# Flight_Controller.net
KiCad netlist of a schematic drawn in Altium Designer
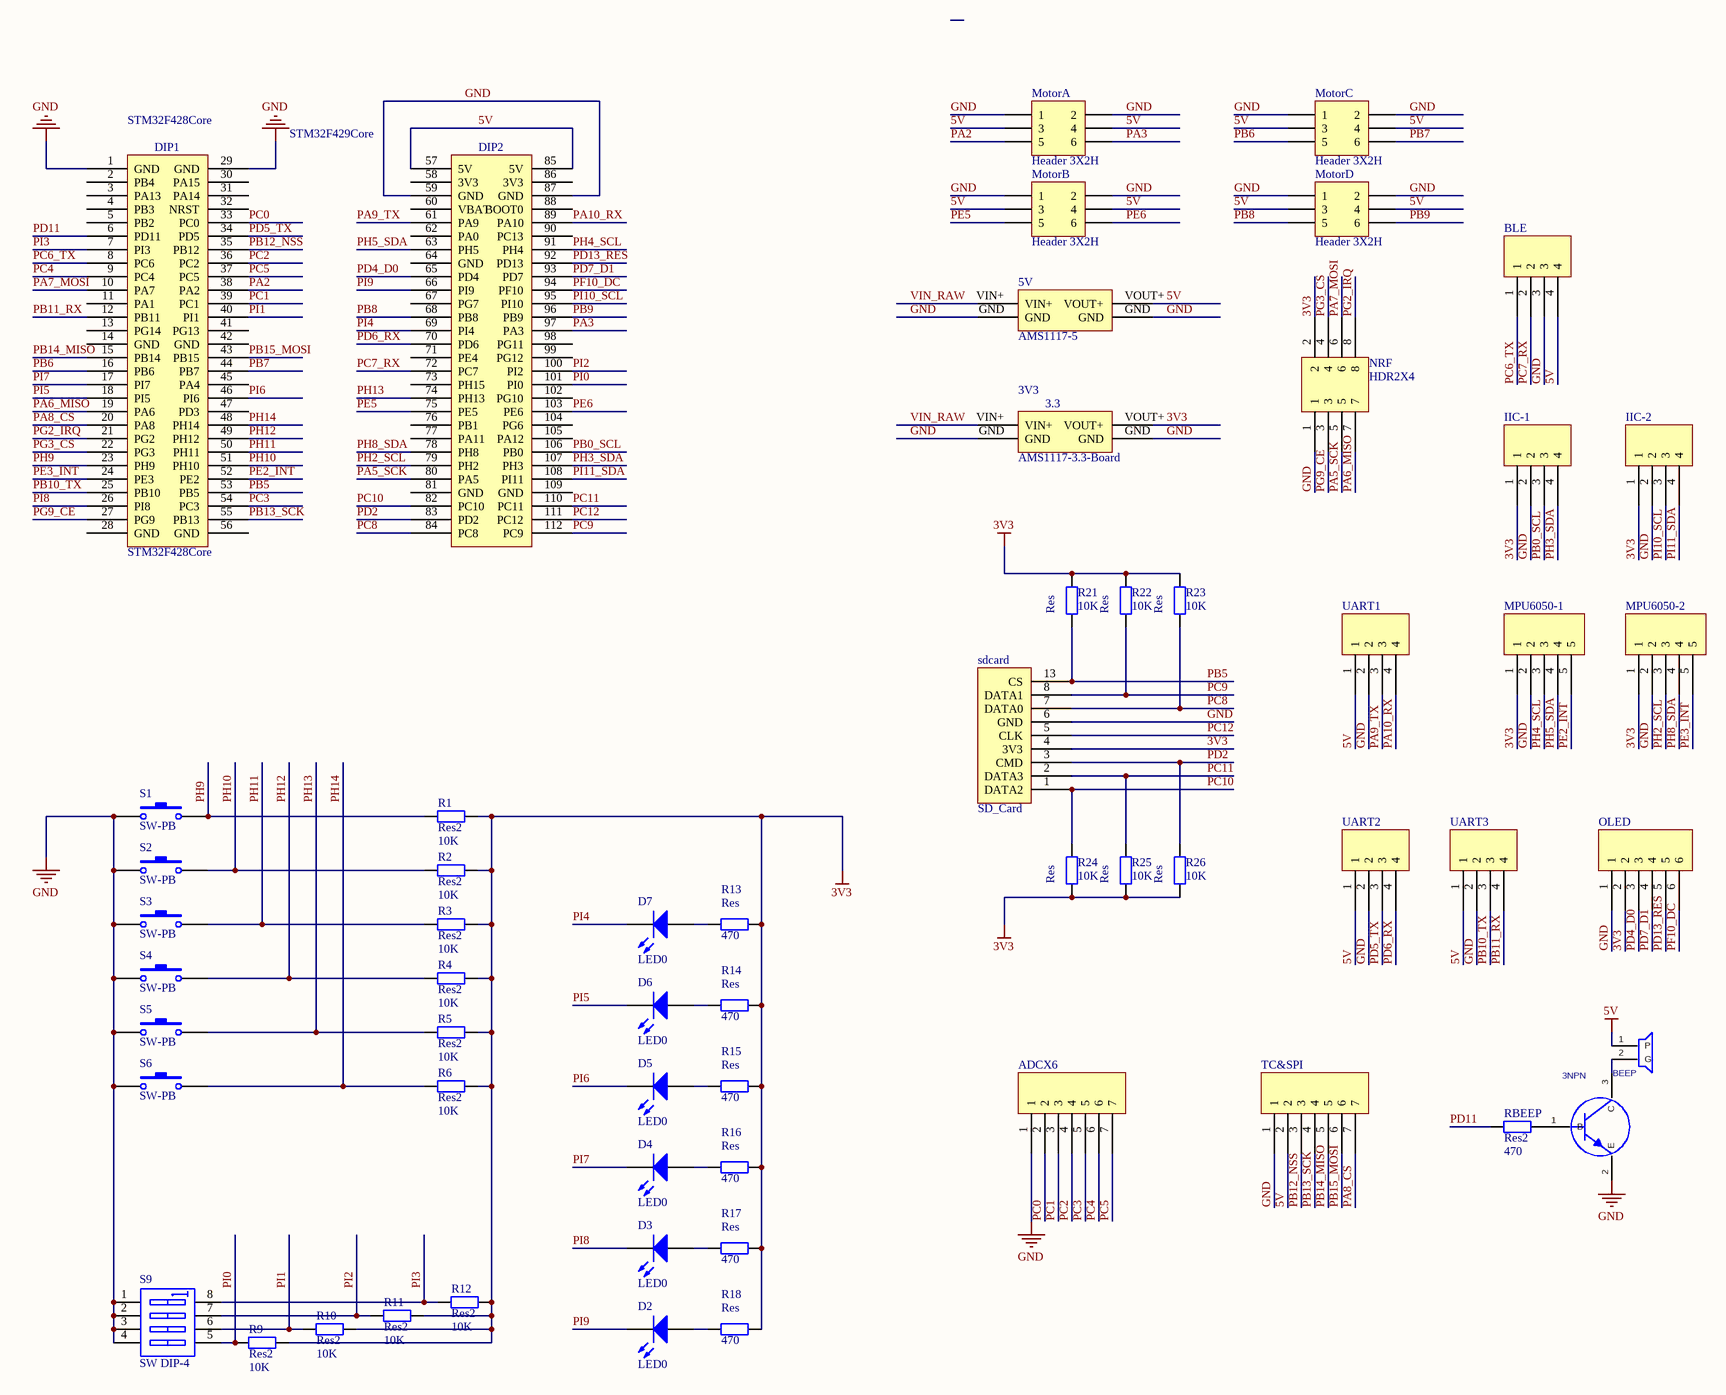
[diagram p0: Flight_Controller.SchDoc]

(export (version "E")
  (design (tool "Eeschema 10.0.6"))
  (components
    (comp (ref "3NPN") (value "NPN") (footprint "3NPN") (libsource (lib "Flight_Controller") (part "3NPN")))
    (comp (ref "3V3")
      (value "AMS1117-3.3-Board")
      (footprint "AMS1117-3.3-Board")
      (libsource (lib "Flight_Controller") (part "AMS1117-3.3-Board"))
    )
    (comp (ref "5V")
      (value "AMS1117-5")
      (footprint "AMS1117-5-Board - duplicate")
      (libsource (lib "Flight_Controller") (part "AMS1117-5"))
    )
    (comp (ref "ADCX6")
      (value "HDR1X7")
      (footprint "HDR1X7")
      (libsource (lib "Flight_Controller") (part "HDR1X7"))
    )
    (comp (ref "BEEP")
      (value "BEEP-9.5X5.5")
      (footprint "BUZZER")
      (libsource (lib "Flight_Controller") (part "BEEP-9.5X5.5"))
    )
    (comp (ref "BLE")
      (value "HDR1X4")
      (footprint "HDR1X4")
      (libsource (lib "Flight_Controller") (part "HDR1X4"))
    )
    (comp (ref "D2")
      (value "LED0")
      (footprint "0805LED")
      (description "Typical INFRARED GaAs LED")
      (fields (field (name "PUBLISHER") "Altium Limited"))
      (libsource (lib "Miscellaneous Devices") (part "LED0"))
    )
    (comp (ref "D3")
      (value "LED0")
      (footprint "0805LED")
      (description "Typical INFRARED GaAs LED")
      (fields (field (name "PUBLISHER") "Altium Limited"))
      (libsource (lib "Miscellaneous Devices") (part "LED0"))
    )
    (comp (ref "D4")
      (value "LED0")
      (footprint "0805LED")
      (description "Typical INFRARED GaAs LED")
      (fields (field (name "PUBLISHER") "Altium Limited"))
      (libsource (lib "Miscellaneous Devices") (part "LED0"))
    )
    (comp (ref "D5")
      (value "LED0")
      (footprint "0805LED")
      (description "Typical INFRARED GaAs LED")
      (fields (field (name "PUBLISHER") "Altium Limited"))
      (libsource (lib "Miscellaneous Devices") (part "LED0"))
    )
    (comp (ref "D6")
      (value "LED0")
      (footprint "0805LED")
      (description "Typical INFRARED GaAs LED")
      (fields (field (name "PUBLISHER") "Altium Limited"))
      (libsource (lib "Miscellaneous Devices") (part "LED0"))
    )
    (comp (ref "D7")
      (value "LED0")
      (footprint "0805LED")
      (description "Typical INFRARED GaAs LED")
      (fields (field (name "PUBLISHER") "Altium Limited"))
      (libsource (lib "Miscellaneous Devices") (part "LED0"))
    )
    (comp (ref "IIC-1")
      (value "HDR1X4")
      (footprint "HDR1X4")
      (libsource (lib "Flight_Controller") (part "HDR1X4"))
    )
    (comp (ref "IIC-2")
      (value "HDR1X4")
      (footprint "HDR1X4")
      (libsource (lib "Flight_Controller") (part "HDR1X4"))
    )
    (comp (ref "MotorA")
      (value "Header 3X2H")
      (footprint "HDR2X3")
      (description "Header, 3-Pin, Dual row, Right Angle")
      (fields (field (name "PUBLISHER") "Altium Limited"))
      (libsource (lib "Miscellaneous Connectors") (part "Header 3X2H"))
    )
    (comp (ref "MotorB")
      (value "Header 3X2H")
      (footprint "HDR2X3")
      (description "Header, 3-Pin, Dual row, Right Angle")
      (fields (field (name "PUBLISHER") "Altium Limited"))
      (libsource (lib "Miscellaneous Connectors") (part "Header 3X2H"))
    )
    (comp (ref "MotorC")
      (value "Header 3X2H")
      (footprint "HDR2X3")
      (description "Header, 3-Pin, Dual row, Right Angle")
      (fields (field (name "PUBLISHER") "Altium Limited"))
      (libsource (lib "Miscellaneous Connectors") (part "Header 3X2H"))
    )
    (comp (ref "MotorD")
      (value "Header 3X2H")
      (footprint "HDR2X3")
      (description "Header, 3-Pin, Dual row, Right Angle")
      (fields (field (name "PUBLISHER") "Altium Limited"))
      (libsource (lib "Miscellaneous Connectors") (part "Header 3X2H"))
    )
    (comp (ref "MPU6050-1")
      (value "HDR1X5")
      (footprint "HDR1X5")
      (libsource (lib "Flight_Controller") (part "HDR1X5"))
    )
    (comp (ref "MPU6050-2")
      (value "HDR1X5")
      (footprint "HDR1X5")
      (libsource (lib "Flight_Controller") (part "HDR1X5"))
    )
    (comp (ref "NRF")
      (value "HDR2X4")
      (footprint "HDR2X4")
      (libsource (lib "Flight_Controller") (part "HDR2X4"))
    )
    (comp (ref "OLED")
      (value "HDR1X6")
      (footprint "HDR1X6")
      (libsource (lib "Flight_Controller") (part "HDR1X6"))
    )
    (comp (ref "R1")
      (value "Res2")
      (footprint "0805")
      (description "Resistor")
      (fields (field (name "ALTIUM_VALUE") "10K") (field (name "PUBLISHER") "Altium Limited"))
      (libsource (lib "Miscellaneous Devices") (part "Res2"))
    )
    (comp (ref "R2")
      (value "Res2")
      (footprint "0805")
      (description "Resistor")
      (fields (field (name "ALTIUM_VALUE") "10K") (field (name "PUBLISHER") "Altium Limited"))
      (libsource (lib "Miscellaneous Devices") (part "Res2"))
    )
    (comp (ref "R3")
      (value "Res2")
      (footprint "0805")
      (description "Resistor")
      (fields (field (name "ALTIUM_VALUE") "10K") (field (name "PUBLISHER") "Altium Limited"))
      (libsource (lib "Miscellaneous Devices") (part "Res2"))
    )
    (comp (ref "R4")
      (value "Res2")
      (footprint "0805")
      (description "Resistor")
      (fields (field (name "ALTIUM_VALUE") "10K") (field (name "PUBLISHER") "Altium Limited"))
      (libsource (lib "Miscellaneous Devices") (part "Res2"))
    )
    (comp (ref "R5")
      (value "Res2")
      (footprint "0805")
      (description "Resistor")
      (fields (field (name "ALTIUM_VALUE") "10K") (field (name "PUBLISHER") "Altium Limited"))
      (libsource (lib "Miscellaneous Devices") (part "Res2"))
    )
    (comp (ref "R6")
      (value "Res2")
      (footprint "0805")
      (description "Resistor")
      (fields (field (name "ALTIUM_VALUE") "10K") (field (name "PUBLISHER") "Altium Limited"))
      (libsource (lib "Miscellaneous Devices") (part "Res2"))
    )
    (comp (ref "R9")
      (value "Res2")
      (footprint "Flight_Controller:0805")
      (description "Resistor")
      (fields (field (name "ALTIUM_VALUE") "10K") (field (name "PUBLISHER") "Altium Limited"))
      (libsource (lib "Miscellaneous Devices") (part "Res2"))
    )
    (comp (ref "R10")
      (value "Res2")
      (footprint "0805")
      (description "Resistor")
      (fields (field (name "ALTIUM_VALUE") "10K") (field (name "PUBLISHER") "Altium Limited"))
      (libsource (lib "Miscellaneous Devices") (part "Res2"))
    )
    (comp (ref "R11")
      (value "Res2")
      (footprint "0805")
      (description "Resistor")
      (fields (field (name "ALTIUM_VALUE") "10K") (field (name "PUBLISHER") "Altium Limited"))
      (libsource (lib "Miscellaneous Devices") (part "Res2"))
    )
    (comp (ref "R12")
      (value "Res2")
      (footprint "0805")
      (description "Resistor")
      (fields (field (name "ALTIUM_VALUE") "10K") (field (name "PUBLISHER") "Altium Limited"))
      (libsource (lib "Miscellaneous Devices") (part "Res2"))
    )
    (comp (ref "R13") (value "470") (footprint "0805") (libsource (lib "") (part "res_1")))
    (comp (ref "R14") (value "470") (footprint "0805") (libsource (lib "") (part "res_1")))
    (comp (ref "R15") (value "470") (footprint "0805") (libsource (lib "") (part "res_1")))
    (comp (ref "R16") (value "470") (footprint "0805") (libsource (lib "") (part "res_1")))
    (comp (ref "R17") (value "470") (footprint "0805") (libsource (lib "") (part "res_1")))
    (comp (ref "R18") (value "470") (footprint "0805") (libsource (lib "") (part "res_1")))
    (comp (ref "R21") (value "10K") (footprint "0805") (libsource (lib "Flight_Controller") (part "res")))
    (comp (ref "R22") (value "10K") (footprint "0805") (libsource (lib "Flight_Controller") (part "res")))
    (comp (ref "R23") (value "10K") (footprint "0805") (libsource (lib "Flight_Controller") (part "res")))
    (comp (ref "R24") (value "10K") (footprint "0805") (libsource (lib "Flight_Controller") (part "res")))
    (comp (ref "R25") (value "10K") (footprint "0805") (libsource (lib "Flight_Controller") (part "res")))
    (comp (ref "R26") (value "10K") (footprint "0805") (libsource (lib "Flight_Controller") (part "res")))
    (comp (ref "RBEEP")
      (value "Res2")
      (footprint "0805")
      (description "Resistor")
      (fields (field (name "ALTIUM_VALUE") "470") (field (name "PUBLISHER") "Altium Limited"))
      (libsource (lib "Miscellaneous Devices") (part "Res2"))
    )
    (comp (ref "S1")
      (value "SW-PB")
      (footprint "Button")
      (description "Switch")
      (fields (field (name "PUBLISHER") "Altium Limited"))
      (libsource (lib "Miscellaneous Devices") (part "SW-PB"))
    )
    (comp (ref "S2")
      (value "SW-PB")
      (footprint "Button")
      (description "Switch")
      (fields (field (name "PUBLISHER") "Altium Limited"))
      (libsource (lib "Miscellaneous Devices") (part "SW-PB"))
    )
    (comp (ref "S3")
      (value "SW-PB")
      (footprint "Button")
      (description "Switch")
      (fields (field (name "PUBLISHER") "Altium Limited"))
      (libsource (lib "Miscellaneous Devices") (part "SW-PB"))
    )
    (comp (ref "S4")
      (value "SW-PB")
      (footprint "Button")
      (description "Switch")
      (fields (field (name "PUBLISHER") "Altium Limited"))
      (libsource (lib "Miscellaneous Devices") (part "SW-PB"))
    )
    (comp (ref "S5")
      (value "SW-PB")
      (footprint "Button")
      (description "Switch")
      (fields (field (name "PUBLISHER") "Altium Limited"))
      (libsource (lib "Miscellaneous Devices") (part "SW-PB"))
    )
    (comp (ref "S6")
      (value "SW-PB")
      (footprint "Button")
      (description "Switch")
      (fields (field (name "PUBLISHER") "Altium Limited"))
      (libsource (lib "Miscellaneous Devices") (part "SW-PB"))
    )
    (comp (ref "S9")
      (value "SW DIP-4")
      (footprint "bmkgtp")
      (description "DIP Switch, 4 Position, SPST")
      (fields (field (name "PUBLISHER") "Altium Limited"))
      (libsource (lib "Miscellaneous Devices") (part "SW DIP-4"))
    )
    (comp (ref "sdcard")
      (value "SD_Card")
      (footprint "SD_Card")
      (libsource (lib "Flight_Controller") (part "SD_Card"))
    )
    (comp (ref "STM32F428Core")
      (value "STM32F428Core")
      (footprint "F429")
      (libsource (lib "Flight_Controller") (part "STM32F428Core"))
    )
    (comp (ref "TC&SPI")
      (value "HDR1X7")
      (footprint "HDR1X7")
      (libsource (lib "Flight_Controller") (part "HDR1X7"))
    )
    (comp (ref "UART1")
      (value "HDR1X4")
      (footprint "HDR1X4")
      (libsource (lib "Flight_Controller") (part "HDR1X4"))
    )
    (comp (ref "UART2")
      (value "HDR1X4")
      (footprint "HDR1X4")
      (libsource (lib "Flight_Controller") (part "HDR1X4"))
    )
    (comp (ref "UART3")
      (value "HDR1X4")
      (footprint "HDR1X4")
      (libsource (lib "Flight_Controller") (part "HDR1X4"))
    )
  )
  (nets
    (net (code "1") (name "/PA2") (class "Default")
      (node (ref "MotorA") (pin "5") (pinfunction "5_5") (pintype "passive"))
      (node (ref "STM32F428Core") (pin "38") (pinfunction "PA2_38") (pintype "passive"))
    )
    (net (code "2") (name "/PA3") (class "Default")
      (node (ref "MotorA") (pin "6") (pinfunction "6_6") (pintype "passive"))
      (node (ref "STM32F428Core") (pin "97") (pinfunction "PA3_97") (pintype "passive"))
    )
    (net (code "3") (name "/PA5_SCK") (class "Default")
      (node (ref "NRF") (pin "5") (pinfunction "5_5") (pintype "passive"))
      (node (ref "STM32F428Core") (pin "80") (pinfunction "PA5_80") (pintype "passive"))
    )
    (net (code "4") (name "/PA6_MISO") (class "Default")
      (node (ref "NRF") (pin "7") (pinfunction "7_7") (pintype "passive"))
      (node (ref "STM32F428Core") (pin "19") (pinfunction "PA6_19") (pintype "passive"))
    )
    (net (code "5") (name "/PA7_MOSI") (class "Default")
      (node (ref "NRF") (pin "6") (pinfunction "6_6") (pintype "passive"))
      (node (ref "STM32F428Core") (pin "10") (pinfunction "PA7_10") (pintype "passive"))
    )
    (net (code "6") (name "/PA8_CS") (class "Default")
      (node (ref "STM32F428Core") (pin "20") (pinfunction "PA8_20") (pintype "passive"))
      (node (ref "TC&SPI") (pin "7") (pinfunction "7_7") (pintype "passive"))
    )
    (net (code "7") (name "/PA9_TX") (class "Default")
      (node (ref "STM32F428Core") (pin "61") (pinfunction "PA9_61") (pintype "passive"))
      (node (ref "UART1") (pin "3") (pinfunction "3_3") (pintype "passive"))
    )
    (net (code "8") (name "/PA10_RX") (class "Default")
      (node (ref "STM32F428Core") (pin "89") (pinfunction "PA10_89") (pintype "passive"))
      (node (ref "UART1") (pin "4") (pinfunction "4_4") (pintype "passive"))
    )
    (net (code "9") (name "/PB0_SCL") (class "Default")
      (node (ref "IIC-1") (pin "3") (pinfunction "3_3") (pintype "passive"))
      (node (ref "STM32F428Core") (pin "106") (pinfunction "PB0_106") (pintype "passive"))
    )
    (net (code "10") (name "/PB5") (class "Default")
      (node (ref "R21") (pin "1") (pinfunction "1_1") (pintype "passive"))
      (node (ref "STM32F428Core") (pin "53") (pinfunction "PB5_53") (pintype "passive"))
      (node (ref "sdcard") (pin "13") (pinfunction "CS_13") (pintype "passive"))
    )
    (net (code "11") (name "/PB6") (class "Default")
      (node (ref "MotorC") (pin "5") (pinfunction "5_5") (pintype "passive"))
      (node (ref "STM32F428Core") (pin "16") (pinfunction "PB6_16") (pintype "passive"))
    )
    (net (code "12") (name "/PB7") (class "Default")
      (node (ref "MotorC") (pin "6") (pinfunction "6_6") (pintype "passive"))
      (node (ref "STM32F428Core") (pin "44") (pinfunction "PB7_44") (pintype "passive"))
    )
    (net (code "13") (name "/PB8") (class "Default")
      (node (ref "MotorD") (pin "5") (pinfunction "5_5") (pintype "passive"))
      (node (ref "STM32F428Core") (pin "68") (pinfunction "PB8_68") (pintype "passive"))
    )
    (net (code "14") (name "/PB9") (class "Default")
      (node (ref "MotorD") (pin "6") (pinfunction "6_6") (pintype "passive"))
      (node (ref "STM32F428Core") (pin "96") (pinfunction "PB9_96") (pintype "passive"))
    )
    (net (code "15") (name "/PB10_TX") (class "Default")
      (node (ref "STM32F428Core") (pin "25") (pinfunction "PB10_25") (pintype "passive"))
      (node (ref "UART3") (pin "3") (pinfunction "3_3") (pintype "passive"))
    )
    (net (code "16") (name "/PB11_RX") (class "Default")
      (node (ref "STM32F428Core") (pin "12") (pinfunction "PB11_12") (pintype "passive"))
      (node (ref "UART3") (pin "4") (pinfunction "4_4") (pintype "passive"))
    )
    (net (code "17") (name "/PB12_NSS") (class "Default")
      (node (ref "STM32F428Core") (pin "35") (pinfunction "PB12_35") (pintype "passive"))
      (node (ref "TC&SPI") (pin "3") (pinfunction "3_3") (pintype "passive"))
    )
    (net (code "18") (name "/PB13_SCK") (class "Default")
      (node (ref "STM32F428Core") (pin "55") (pinfunction "PB13_55") (pintype "passive"))
      (node (ref "TC&SPI") (pin "4") (pinfunction "4_4") (pintype "passive"))
    )
    (net (code "19") (name "/PB14_MISO") (class "Default")
      (node (ref "STM32F428Core") (pin "15") (pinfunction "PB14_15") (pintype "passive"))
      (node (ref "TC&SPI") (pin "5") (pinfunction "5_5") (pintype "passive"))
    )
    (net (code "20") (name "/PB15_MOSI") (class "Default")
      (node (ref "STM32F428Core") (pin "43") (pinfunction "PB15_43") (pintype "passive"))
      (node (ref "TC&SPI") (pin "6") (pinfunction "6_6") (pintype "passive"))
    )
    (net (code "21") (name "/PC0") (class "Default")
      (node (ref "ADCX6") (pin "2") (pinfunction "2_2") (pintype "passive"))
      (node (ref "STM32F428Core") (pin "33") (pinfunction "PC0_33") (pintype "passive"))
    )
    (net (code "22") (name "/PC1") (class "Default")
      (node (ref "ADCX6") (pin "3") (pinfunction "3_3") (pintype "passive"))
      (node (ref "STM32F428Core") (pin "39") (pinfunction "PC1_39") (pintype "passive"))
    )
    (net (code "23") (name "/PC2") (class "Default")
      (node (ref "ADCX6") (pin "4") (pinfunction "4_4") (pintype "passive"))
      (node (ref "STM32F428Core") (pin "36") (pinfunction "PC2_36") (pintype "passive"))
    )
    (net (code "24") (name "/PC3") (class "Default")
      (node (ref "ADCX6") (pin "5") (pinfunction "5_5") (pintype "passive"))
      (node (ref "STM32F428Core") (pin "54") (pinfunction "PC3_54") (pintype "passive"))
    )
    (net (code "25") (name "/PC4") (class "Default")
      (node (ref "ADCX6") (pin "6") (pinfunction "6_6") (pintype "passive"))
      (node (ref "STM32F428Core") (pin "9") (pinfunction "PC4_9") (pintype "passive"))
    )
    (net (code "26") (name "/PC5") (class "Default")
      (node (ref "ADCX6") (pin "7") (pinfunction "7_7") (pintype "passive"))
      (node (ref "STM32F428Core") (pin "37") (pinfunction "PC5_37") (pintype "passive"))
    )
    (net (code "27") (name "/PC6_TX") (class "Default")
      (node (ref "BLE") (pin "1") (pinfunction "1_1") (pintype "passive"))
      (node (ref "STM32F428Core") (pin "8") (pinfunction "PC6_8") (pintype "passive"))
    )
    (net (code "28") (name "/PC7_RX") (class "Default")
      (node (ref "BLE") (pin "2") (pinfunction "2_2") (pintype "passive"))
      (node (ref "STM32F428Core") (pin "72") (pinfunction "PC7_72") (pintype "passive"))
    )
    (net (code "29") (name "/PC8") (class "Default")
      (node (ref "R23") (pin "1") (pinfunction "1_1") (pintype "passive"))
      (node (ref "STM32F428Core") (pin "84") (pinfunction "PC8_84") (pintype "passive"))
      (node (ref "sdcard") (pin "7") (pinfunction "DATA0_7") (pintype "passive"))
    )
    (net (code "30") (name "/PC9") (class "Default")
      (node (ref "R22") (pin "1") (pinfunction "1_1") (pintype "passive"))
      (node (ref "STM32F428Core") (pin "112") (pinfunction "PC9_112") (pintype "passive"))
      (node (ref "sdcard") (pin "8") (pinfunction "DATA1_8") (pintype "passive"))
    )
    (net (code "31") (name "/PC10") (class "Default")
      (node (ref "R24") (pin "2") (pinfunction "2_2") (pintype "passive"))
      (node (ref "STM32F428Core") (pin "82") (pinfunction "PC10_82") (pintype "passive"))
      (node (ref "sdcard") (pin "1") (pinfunction "DATA2_1") (pintype "passive"))
    )
    (net (code "32") (name "/PC11") (class "Default")
      (node (ref "R25") (pin "2") (pinfunction "2_2") (pintype "passive"))
      (node (ref "STM32F428Core") (pin "110") (pinfunction "PC11_110") (pintype "passive"))
      (node (ref "sdcard") (pin "2") (pinfunction "DATA3_2") (pintype "passive"))
    )
    (net (code "33") (name "/PC12") (class "Default")
      (node (ref "STM32F428Core") (pin "111") (pinfunction "PC12_111") (pintype "passive"))
      (node (ref "sdcard") (pin "5") (pinfunction "CLK_5") (pintype "passive"))
    )
    (net (code "34") (name "/PD2") (class "Default")
      (node (ref "R26") (pin "2") (pinfunction "2_2") (pintype "passive"))
      (node (ref "STM32F428Core") (pin "83") (pinfunction "PD2_83") (pintype "passive"))
      (node (ref "sdcard") (pin "3") (pinfunction "CMD_3") (pintype "passive"))
    )
    (net (code "35") (name "/PD4_D0") (class "Default")
      (node (ref "OLED") (pin "3") (pinfunction "3_3") (pintype "passive"))
      (node (ref "STM32F428Core") (pin "65") (pinfunction "PD4_65") (pintype "passive"))
    )
    (net (code "36") (name "/PD5_TX") (class "Default")
      (node (ref "STM32F428Core") (pin "34") (pinfunction "PD5_34") (pintype "passive"))
      (node (ref "UART2") (pin "3") (pinfunction "3_3") (pintype "passive"))
    )
    (net (code "37") (name "/PD6_RX") (class "Default")
      (node (ref "STM32F428Core") (pin "70") (pinfunction "PD6_70") (pintype "passive"))
      (node (ref "UART2") (pin "4") (pinfunction "4_4") (pintype "passive"))
    )
    (net (code "38") (name "/PD7_D1") (class "Default")
      (node (ref "OLED") (pin "4") (pinfunction "4_4") (pintype "passive"))
      (node (ref "STM32F428Core") (pin "93") (pinfunction "PD7_93") (pintype "passive"))
    )
    (net (code "39") (name "/PD11") (class "Default")
      (node (ref "RBEEP") (pin "1") (pinfunction "1_1") (pintype "passive"))
      (node (ref "STM32F428Core") (pin "6") (pinfunction "PD11_6") (pintype "passive"))
    )
    (net (code "40") (name "/PD13_RES") (class "Default")
      (node (ref "OLED") (pin "5") (pinfunction "5_5") (pintype "passive"))
      (node (ref "STM32F428Core") (pin "92") (pinfunction "PD13_92") (pintype "passive"))
    )
    (net (code "41") (name "/PE2_INT") (class "Default")
      (node (ref "MPU6050-1") (pin "5") (pinfunction "5_5") (pintype "passive"))
      (node (ref "STM32F428Core") (pin "52") (pinfunction "PE2_52") (pintype "passive"))
    )
    (net (code "42") (name "/PE3_INT") (class "Default")
      (node (ref "MPU6050-2") (pin "5") (pinfunction "5_5") (pintype "passive"))
      (node (ref "STM32F428Core") (pin "24") (pinfunction "PE3_24") (pintype "passive"))
    )
    (net (code "43") (name "/PE5") (class "Default")
      (node (ref "MotorB") (pin "5") (pinfunction "5_5") (pintype "passive"))
      (node (ref "STM32F428Core") (pin "75") (pinfunction "PE5_75") (pintype "passive"))
    )
    (net (code "44") (name "/PE6") (class "Default")
      (node (ref "MotorB") (pin "6") (pinfunction "6_6") (pintype "passive"))
      (node (ref "STM32F428Core") (pin "103") (pinfunction "PE6_103") (pintype "passive"))
    )
    (net (code "45") (name "/PF10_DC") (class "Default")
      (node (ref "OLED") (pin "6") (pinfunction "6_6") (pintype "passive"))
      (node (ref "STM32F428Core") (pin "94") (pinfunction "PF10_94") (pintype "passive"))
    )
    (net (code "46") (name "/PG2_IRQ") (class "Default")
      (node (ref "NRF") (pin "8") (pinfunction "8_8") (pintype "passive"))
      (node (ref "STM32F428Core") (pin "21") (pinfunction "PG2_21") (pintype "passive"))
    )
    (net (code "47") (name "/PG3_CS") (class "Default")
      (node (ref "NRF") (pin "4") (pinfunction "4_4") (pintype "passive"))
      (node (ref "STM32F428Core") (pin "22") (pinfunction "PG3_22") (pintype "passive"))
    )
    (net (code "48") (name "/PG9_CE") (class "Default")
      (node (ref "NRF") (pin "3") (pinfunction "3_3") (pintype "passive"))
      (node (ref "STM32F428Core") (pin "27") (pinfunction "PG9_27") (pintype "passive"))
    )
    (net (code "49") (name "/PH2_SCL") (class "Default")
      (node (ref "MPU6050-2") (pin "3") (pinfunction "3_3") (pintype "passive"))
      (node (ref "STM32F428Core") (pin "79") (pinfunction "PH2_79") (pintype "passive"))
    )
    (net (code "50") (name "/PH3_SDA") (class "Default")
      (node (ref "IIC-1") (pin "4") (pinfunction "4_4") (pintype "passive"))
      (node (ref "STM32F428Core") (pin "107") (pinfunction "PH3_107") (pintype "passive"))
    )
    (net (code "51") (name "/PH4_SCL") (class "Default")
      (node (ref "MPU6050-1") (pin "3") (pinfunction "3_3") (pintype "passive"))
      (node (ref "STM32F428Core") (pin "91") (pinfunction "PH4_91") (pintype "passive"))
    )
    (net (code "52") (name "/PH5_SDA") (class "Default")
      (node (ref "MPU6050-1") (pin "4") (pinfunction "4_4") (pintype "passive"))
      (node (ref "STM32F428Core") (pin "63") (pinfunction "PH5_63") (pintype "passive"))
    )
    (net (code "53") (name "/PH8_SDA") (class "Default")
      (node (ref "MPU6050-2") (pin "4") (pinfunction "4_4") (pintype "passive"))
      (node (ref "STM32F428Core") (pin "78") (pinfunction "PH8_78") (pintype "passive"))
    )
    (net (code "54") (name "/PH9") (class "Default")
      (node (ref "R1") (pin "1") (pinfunction "1_1") (pintype "passive"))
      (node (ref "S1") (pin "2") (pinfunction "2_2") (pintype "passive"))
      (node (ref "STM32F428Core") (pin "23") (pinfunction "PH9_23") (pintype "passive"))
    )
    (net (code "55") (name "/PH10") (class "Default")
      (node (ref "R2") (pin "1") (pinfunction "1_1") (pintype "passive"))
      (node (ref "S2") (pin "2") (pinfunction "2_2") (pintype "passive"))
      (node (ref "STM32F428Core") (pin "51") (pinfunction "PH10_51") (pintype "passive"))
    )
    (net (code "56") (name "/PH11") (class "Default")
      (node (ref "R3") (pin "1") (pinfunction "1_1") (pintype "passive"))
      (node (ref "S3") (pin "2") (pinfunction "2_2") (pintype "passive"))
      (node (ref "STM32F428Core") (pin "50") (pinfunction "PH11_50") (pintype "passive"))
    )
    (net (code "57") (name "/PH12") (class "Default")
      (node (ref "R4") (pin "1") (pinfunction "1_1") (pintype "passive"))
      (node (ref "S4") (pin "2") (pinfunction "2_2") (pintype "passive"))
      (node (ref "STM32F428Core") (pin "49") (pinfunction "PH12_49") (pintype "passive"))
    )
    (net (code "58") (name "/PH13") (class "Default")
      (node (ref "R5") (pin "1") (pinfunction "1_1") (pintype "passive"))
      (node (ref "S5") (pin "2") (pinfunction "2_2") (pintype "passive"))
      (node (ref "STM32F428Core") (pin "74") (pinfunction "PH13_74") (pintype "passive"))
    )
    (net (code "59") (name "/PH14") (class "Default")
      (node (ref "R6") (pin "1") (pinfunction "1_1") (pintype "passive"))
      (node (ref "S6") (pin "2") (pinfunction "2_2") (pintype "passive"))
      (node (ref "STM32F428Core") (pin "48") (pinfunction "PH14_48") (pintype "passive"))
    )
    (net (code "60") (name "/PI0") (class "Default")
      (node (ref "R9") (pin "1") (pinfunction "1_1") (pintype "passive"))
      (node (ref "S9") (pin "5") (pinfunction "B4_5") (pintype "passive"))
      (node (ref "STM32F428Core") (pin "101") (pinfunction "PI0_101") (pintype "passive"))
    )
    (net (code "61") (name "/PI1") (class "Default")
      (node (ref "R10") (pin "1") (pinfunction "1_1") (pintype "passive"))
      (node (ref "S9") (pin "6") (pinfunction "B3_6") (pintype "passive"))
      (node (ref "STM32F428Core") (pin "40") (pinfunction "PI1_40") (pintype "passive"))
    )
    (net (code "62") (name "/PI2") (class "Default")
      (node (ref "R11") (pin "1") (pinfunction "1_1") (pintype "passive"))
      (node (ref "S9") (pin "7") (pinfunction "B2_7") (pintype "passive"))
      (node (ref "STM32F428Core") (pin "100") (pinfunction "PI2_100") (pintype "passive"))
    )
    (net (code "63") (name "/PI3") (class "Default")
      (node (ref "R12") (pin "1") (pinfunction "1_1") (pintype "passive"))
      (node (ref "S9") (pin "8") (pinfunction "B1_8") (pintype "passive"))
      (node (ref "STM32F428Core") (pin "7") (pinfunction "PI3_7") (pintype "passive"))
    )
    (net (code "64") (name "/PI4") (class "Default")
      (node (ref "D7") (pin "2") (pinfunction "K_2") (pintype "passive"))
      (node (ref "STM32F428Core") (pin "69") (pinfunction "PI4_69") (pintype "passive"))
    )
    (net (code "65") (name "/PI5") (class "Default")
      (node (ref "D6") (pin "2") (pinfunction "K_2") (pintype "passive"))
      (node (ref "STM32F428Core") (pin "18") (pinfunction "PI5_18") (pintype "passive"))
    )
    (net (code "66") (name "/PI6") (class "Default")
      (node (ref "D5") (pin "2") (pinfunction "K_2") (pintype "passive"))
      (node (ref "STM32F428Core") (pin "46") (pinfunction "PI6_46") (pintype "passive"))
    )
    (net (code "67") (name "/PI7") (class "Default")
      (node (ref "D4") (pin "2") (pinfunction "K_2") (pintype "passive"))
      (node (ref "STM32F428Core") (pin "17") (pinfunction "PI7_17") (pintype "passive"))
    )
    (net (code "68") (name "/PI8") (class "Default")
      (node (ref "D3") (pin "2") (pinfunction "K_2") (pintype "passive"))
      (node (ref "STM32F428Core") (pin "26") (pinfunction "PI8_26") (pintype "passive"))
    )
    (net (code "69") (name "/PI9") (class "Default")
      (node (ref "D2") (pin "2") (pinfunction "K_2") (pintype "passive"))
      (node (ref "STM32F428Core") (pin "66") (pinfunction "PI9_66") (pintype "passive"))
    )
    (net (code "70") (name "/PI10_SCL") (class "Default")
      (node (ref "IIC-2") (pin "3") (pinfunction "3_3") (pintype "passive"))
      (node (ref "STM32F428Core") (pin "95") (pinfunction "PI10_95") (pintype "passive"))
    )
    (net (code "71") (name "/PI11_SDA") (class "Default")
      (node (ref "IIC-2") (pin "4") (pinfunction "4_4") (pintype "passive"))
      (node (ref "STM32F428Core") (pin "108") (pinfunction "PI11_108") (pintype "passive"))
    )
    (net (code "72") (name "/VIN_RAW") (class "Default")
      (node (ref "3V3") (pin "VIN+") (pinfunction "VIN+_VIN+") (pintype "passive"))
      (node (ref "5V") (pin "VIN+") (pinfunction "VIN+_VIN+") (pintype "passive"))
    )
    (net (code "73") (name "3V3") (class "Default")
      (node (ref "3V3") (pin "VOUT+") (pinfunction "VOUT+_VOUT+") (pintype "passive"))
      (node (ref "IIC-1") (pin "1") (pinfunction "1_1") (pintype "passive"))
      (node (ref "IIC-2") (pin "1") (pinfunction "1_1") (pintype "passive"))
      (node (ref "MPU6050-1") (pin "1") (pinfunction "1_1") (pintype "passive"))
      (node (ref "MPU6050-2") (pin "1") (pinfunction "1_1") (pintype "passive"))
      (node (ref "NRF") (pin "2") (pinfunction "2_2") (pintype "passive"))
      (node (ref "OLED") (pin "2") (pinfunction "2_2") (pintype "passive"))
      (node (ref "R1") (pin "2") (pinfunction "2_2") (pintype "passive"))
      (node (ref "R10") (pin "2") (pinfunction "2_2") (pintype "passive"))
      (node (ref "R11") (pin "2") (pinfunction "2_2") (pintype "passive"))
      (node (ref "R12") (pin "2") (pinfunction "2_2") (pintype "passive"))
      (node (ref "R13") (pin "2") (pinfunction "2_2") (pintype "passive"))
      (node (ref "R14") (pin "2") (pinfunction "2_2") (pintype "passive"))
      (node (ref "R15") (pin "2") (pinfunction "2_2") (pintype "passive"))
      (node (ref "R16") (pin "2") (pinfunction "2_2") (pintype "passive"))
      (node (ref "R17") (pin "2") (pinfunction "2_2") (pintype "passive"))
      (node (ref "R18") (pin "2") (pinfunction "2_2") (pintype "passive"))
      (node (ref "R2") (pin "2") (pinfunction "2_2") (pintype "passive"))
      (node (ref "R21") (pin "2") (pinfunction "2_2") (pintype "passive"))
      (node (ref "R22") (pin "2") (pinfunction "2_2") (pintype "passive"))
      (node (ref "R23") (pin "2") (pinfunction "2_2") (pintype "passive"))
      (node (ref "R24") (pin "1") (pinfunction "1_1") (pintype "passive"))
      (node (ref "R25") (pin "1") (pinfunction "1_1") (pintype "passive"))
      (node (ref "R26") (pin "1") (pinfunction "1_1") (pintype "passive"))
      (node (ref "R3") (pin "2") (pinfunction "2_2") (pintype "passive"))
      (node (ref "R4") (pin "2") (pinfunction "2_2") (pintype "passive"))
      (node (ref "R5") (pin "2") (pinfunction "2_2") (pintype "passive"))
      (node (ref "R6") (pin "2") (pinfunction "2_2") (pintype "passive"))
      (node (ref "R9") (pin "2") (pinfunction "2_2") (pintype "passive"))
      (node (ref "sdcard") (pin "4") (pinfunction "3V3_4") (pintype "passive"))
    )
    (net (code "74") (name "5V") (class "Default")
      (node (ref "5V") (pin "VOUT+") (pinfunction "VOUT+_VOUT+") (pintype "passive"))
      (node (ref "BEEP") (pin "1") (pinfunction "P_1") (pintype "passive"))
      (node (ref "BLE") (pin "4") (pinfunction "4_4") (pintype "passive"))
      (node (ref "MotorA") (pin "3") (pinfunction "3_3") (pintype "passive"))
      (node (ref "MotorA") (pin "4") (pinfunction "4_4") (pintype "passive"))
      (node (ref "MotorB") (pin "3") (pinfunction "3_3") (pintype "passive"))
      (node (ref "MotorB") (pin "4") (pinfunction "4_4") (pintype "passive"))
      (node (ref "MotorC") (pin "3") (pinfunction "3_3") (pintype "passive"))
      (node (ref "MotorC") (pin "4") (pinfunction "4_4") (pintype "passive"))
      (node (ref "MotorD") (pin "3") (pinfunction "3_3") (pintype "passive"))
      (node (ref "MotorD") (pin "4") (pinfunction "4_4") (pintype "passive"))
      (node (ref "STM32F428Core") (pin "57") (pinfunction "5V_57") (pintype "passive"))
      (node (ref "STM32F428Core") (pin "85") (pinfunction "5V_85") (pintype "passive"))
      (node (ref "TC&SPI") (pin "2") (pinfunction "2_2") (pintype "passive"))
      (node (ref "UART1") (pin "1") (pinfunction "1_1") (pintype "passive"))
      (node (ref "UART2") (pin "1") (pinfunction "1_1") (pintype "passive"))
      (node (ref "UART3") (pin "1") (pinfunction "1_1") (pintype "passive"))
    )
    (net (code "75") (name "GND") (class "Default")
      (node (ref "3NPN") (pin "2") (pinfunction "E_2") (pintype "passive"))
      (node (ref "3V3") (pin "GND") (pinfunction "GND_GND") (pintype "passive"))
      (node (ref "5V") (pin "GND") (pinfunction "GND_GND") (pintype "passive"))
      (node (ref "ADCX6") (pin "1") (pinfunction "1_1") (pintype "passive"))
      (node (ref "BLE") (pin "3") (pinfunction "3_3") (pintype "passive"))
      (node (ref "IIC-1") (pin "2") (pinfunction "2_2") (pintype "passive"))
      (node (ref "IIC-2") (pin "2") (pinfunction "2_2") (pintype "passive"))
      (node (ref "MPU6050-1") (pin "2") (pinfunction "2_2") (pintype "passive"))
      (node (ref "MPU6050-2") (pin "2") (pinfunction "2_2") (pintype "passive"))
      (node (ref "MotorA") (pin "1") (pinfunction "1_1") (pintype "passive"))
      (node (ref "MotorA") (pin "2") (pinfunction "2_2") (pintype "passive"))
      (node (ref "MotorB") (pin "1") (pinfunction "1_1") (pintype "passive"))
      (node (ref "MotorB") (pin "2") (pinfunction "2_2") (pintype "passive"))
      (node (ref "MotorC") (pin "1") (pinfunction "1_1") (pintype "passive"))
      (node (ref "MotorC") (pin "2") (pinfunction "2_2") (pintype "passive"))
      (node (ref "MotorD") (pin "1") (pinfunction "1_1") (pintype "passive"))
      (node (ref "MotorD") (pin "2") (pinfunction "2_2") (pintype "passive"))
      (node (ref "NRF") (pin "1") (pinfunction "1_1") (pintype "passive"))
      (node (ref "OLED") (pin "1") (pinfunction "1_1") (pintype "passive"))
      (node (ref "S1") (pin "1") (pinfunction "1_1") (pintype "passive"))
      (node (ref "S2") (pin "1") (pinfunction "1_1") (pintype "passive"))
      (node (ref "S3") (pin "1") (pinfunction "1_1") (pintype "passive"))
      (node (ref "S4") (pin "1") (pinfunction "1_1") (pintype "passive"))
      (node (ref "S5") (pin "1") (pinfunction "1_1") (pintype "passive"))
      (node (ref "S6") (pin "1") (pinfunction "1_1") (pintype "passive"))
      (node (ref "S9") (pin "1") (pinfunction "A1_1") (pintype "passive"))
      (node (ref "S9") (pin "2") (pinfunction "A2_2") (pintype "passive"))
      (node (ref "S9") (pin "3") (pinfunction "A3_3") (pintype "passive"))
      (node (ref "S9") (pin "4") (pinfunction "A4_4") (pintype "passive"))
      (node (ref "STM32F428Core") (pin "1") (pinfunction "GND_1") (pintype "passive"))
      (node (ref "STM32F428Core") (pin "29") (pinfunction "GND_29") (pintype "passive"))
      (node (ref "STM32F428Core") (pin "59") (pinfunction "GND_59") (pintype "passive"))
      (node (ref "STM32F428Core") (pin "87") (pinfunction "GND_87") (pintype "passive"))
      (node (ref "TC&SPI") (pin "1") (pinfunction "1_1") (pintype "passive"))
      (node (ref "UART1") (pin "2") (pinfunction "2_2") (pintype "passive"))
      (node (ref "UART2") (pin "2") (pinfunction "2_2") (pintype "passive"))
      (node (ref "UART3") (pin "2") (pinfunction "2_2") (pintype "passive"))
      (node (ref "sdcard") (pin "6") (pinfunction "GND_6") (pintype "passive"))
    )
    (net (code "76") (name "Net-(3NPN-B)") (class "Default")
      (node (ref "3NPN") (pin "1") (pinfunction "B_1") (pintype "passive"))
      (node (ref "RBEEP") (pin "2") (pinfunction "2_2") (pintype "passive"))
    )
    (net (code "77") (name "Net-(3NPN-C)") (class "Default")
      (node (ref "3NPN") (pin "3") (pinfunction "C_3") (pintype "passive"))
      (node (ref "BEEP") (pin "2") (pinfunction "G_2") (pintype "passive"))
    )
    (net (code "78") (name "Net-(D2-A)") (class "Default")
      (node (ref "D2") (pin "1") (pinfunction "A_1") (pintype "passive"))
      (node (ref "R18") (pin "1") (pinfunction "1_1") (pintype "passive"))
    )
    (net (code "79") (name "Net-(D3-A)") (class "Default")
      (node (ref "D3") (pin "1") (pinfunction "A_1") (pintype "passive"))
      (node (ref "R17") (pin "1") (pinfunction "1_1") (pintype "passive"))
    )
    (net (code "80") (name "Net-(D4-A)") (class "Default")
      (node (ref "D4") (pin "1") (pinfunction "A_1") (pintype "passive"))
      (node (ref "R16") (pin "1") (pinfunction "1_1") (pintype "passive"))
    )
    (net (code "81") (name "Net-(D5-A)") (class "Default")
      (node (ref "D5") (pin "1") (pinfunction "A_1") (pintype "passive"))
      (node (ref "R15") (pin "1") (pinfunction "1_1") (pintype "passive"))
    )
    (net (code "82") (name "Net-(D6-A)") (class "Default")
      (node (ref "D6") (pin "1") (pinfunction "A_1") (pintype "passive"))
      (node (ref "R14") (pin "1") (pinfunction "1_1") (pintype "passive"))
    )
    (net (code "83") (name "Net-(D7-A)") (class "Default")
      (node (ref "D7") (pin "1") (pinfunction "A_1") (pintype "passive"))
      (node (ref "R13") (pin "1") (pinfunction "1_1") (pintype "passive"))
    )
    (net (code "84") (name "unconnected-(STM32F428Core-3V3-Pad58)") (class "Default")
      (node (ref "STM32F428Core") (pin "58") (pinfunction "3V3_58") (pintype "passive"))
    )
    (net (code "85") (name "unconnected-(STM32F428Core-3V3-Pad86)") (class "Default")
      (node (ref "STM32F428Core") (pin "86") (pinfunction "3V3_86") (pintype "passive"))
    )
    (net (code "86") (name "unconnected-(STM32F428Core-BOOT0-Pad88)") (class "Default")
      (node (ref "STM32F428Core") (pin "88") (pinfunction "BOOT0_88") (pintype "passive"))
    )
    (net (code "87") (name "unconnected-(STM32F428Core-GND-Pad14)") (class "Default")
      (node (ref "STM32F428Core") (pin "14") (pinfunction "GND_14") (pintype "passive"))
    )
    (net (code "88") (name "unconnected-(STM32F428Core-GND-Pad28)") (class "Default")
      (node (ref "STM32F428Core") (pin "28") (pinfunction "GND_28") (pintype "passive"))
    )
    (net (code "89") (name "unconnected-(STM32F428Core-GND-Pad42)") (class "Default")
      (node (ref "STM32F428Core") (pin "42") (pinfunction "GND_42") (pintype "passive"))
    )
    (net (code "90") (name "unconnected-(STM32F428Core-GND-Pad56)") (class "Default")
      (node (ref "STM32F428Core") (pin "56") (pinfunction "GND_56") (pintype "passive"))
    )
    (net (code "91") (name "unconnected-(STM32F428Core-GND-Pad64)") (class "Default")
      (node (ref "STM32F428Core") (pin "64") (pinfunction "GND_64") (pintype "passive"))
    )
    (net (code "92") (name "unconnected-(STM32F428Core-GND-Pad81)") (class "Default")
      (node (ref "STM32F428Core") (pin "81") (pinfunction "GND_81") (pintype "passive"))
    )
    (net (code "93") (name "unconnected-(STM32F428Core-GND-Pad109)") (class "Default")
      (node (ref "STM32F428Core") (pin "109") (pinfunction "GND_109") (pintype "passive"))
    )
    (net (code "94") (name "unconnected-(STM32F428Core-NRST-Pad32)") (class "Default")
      (node (ref "STM32F428Core") (pin "32") (pinfunction "NRST_32") (pintype "passive"))
    )
    (net (code "95") (name "unconnected-(STM32F428Core-PA0-Pad62)") (class "Default")
      (node (ref "STM32F428Core") (pin "62") (pinfunction "PA0_62") (pintype "passive"))
    )
    (net (code "96") (name "unconnected-(STM32F428Core-PA1-Pad11)") (class "Default")
      (node (ref "STM32F428Core") (pin "11") (pinfunction "PA1_11") (pintype "passive"))
    )
    (net (code "97") (name "unconnected-(STM32F428Core-PA4-Pad45)") (class "Default")
      (node (ref "STM32F428Core") (pin "45") (pinfunction "PA4_45") (pintype "passive"))
    )
    (net (code "98") (name "unconnected-(STM32F428Core-PA11-Pad77)") (class "Default")
      (node (ref "STM32F428Core") (pin "77") (pinfunction "PA11_77") (pintype "passive"))
    )
    (net (code "99") (name "unconnected-(STM32F428Core-PA12-Pad105)") (class "Default")
      (node (ref "STM32F428Core") (pin "105") (pinfunction "PA12_105") (pintype "passive"))
    )
    (net (code "100") (name "unconnected-(STM32F428Core-PA13-Pad3)") (class "Default")
      (node (ref "STM32F428Core") (pin "3") (pinfunction "PA13_3") (pintype "passive"))
    )
    (net (code "101") (name "unconnected-(STM32F428Core-PA14-Pad31)") (class "Default")
      (node (ref "STM32F428Core") (pin "31") (pinfunction "PA14_31") (pintype "passive"))
    )
    (net (code "102") (name "unconnected-(STM32F428Core-PA15-Pad30)") (class "Default")
      (node (ref "STM32F428Core") (pin "30") (pinfunction "PA15_30") (pintype "passive"))
    )
    (net (code "103") (name "unconnected-(STM32F428Core-PB1-Pad76)") (class "Default")
      (node (ref "STM32F428Core") (pin "76") (pinfunction "PB1_76") (pintype "passive"))
    )
    (net (code "104") (name "unconnected-(STM32F428Core-PB2-Pad5)") (class "Default")
      (node (ref "STM32F428Core") (pin "5") (pinfunction "PB2_5") (pintype "passive"))
    )
    (net (code "105") (name "unconnected-(STM32F428Core-PB3-Pad4)") (class "Default")
      (node (ref "STM32F428Core") (pin "4") (pinfunction "PB3_4") (pintype "passive"))
    )
    (net (code "106") (name "unconnected-(STM32F428Core-PB4-Pad2)") (class "Default")
      (node (ref "STM32F428Core") (pin "2") (pinfunction "PB4_2") (pintype "passive"))
    )
    (net (code "107") (name "unconnected-(STM32F428Core-PC13-Pad90)") (class "Default")
      (node (ref "STM32F428Core") (pin "90") (pinfunction "PC13_90") (pintype "passive"))
    )
    (net (code "108") (name "unconnected-(STM32F428Core-PD3-Pad47)") (class "Default")
      (node (ref "STM32F428Core") (pin "47") (pinfunction "PD3_47") (pintype "passive"))
    )
    (net (code "109") (name "unconnected-(STM32F428Core-PE4-Pad71)") (class "Default")
      (node (ref "STM32F428Core") (pin "71") (pinfunction "PE4_71") (pintype "passive"))
    )
    (net (code "110") (name "unconnected-(STM32F428Core-PG6-Pad104)") (class "Default")
      (node (ref "STM32F428Core") (pin "104") (pinfunction "PG6_104") (pintype "passive"))
    )
    (net (code "111") (name "unconnected-(STM32F428Core-PG7-Pad67)") (class "Default")
      (node (ref "STM32F428Core") (pin "67") (pinfunction "PG7_67") (pintype "passive"))
    )
    (net (code "112") (name "unconnected-(STM32F428Core-PG10-Pad102)") (class "Default")
      (node (ref "STM32F428Core") (pin "102") (pinfunction "PG10_102") (pintype "passive"))
    )
    (net (code "113") (name "unconnected-(STM32F428Core-PG11-Pad98)") (class "Default")
      (node (ref "STM32F428Core") (pin "98") (pinfunction "PG11_98") (pintype "passive"))
    )
    (net (code "114") (name "unconnected-(STM32F428Core-PG12-Pad99)") (class "Default")
      (node (ref "STM32F428Core") (pin "99") (pinfunction "PG12_99") (pintype "passive"))
    )
    (net (code "115") (name "unconnected-(STM32F428Core-PG13-Pad41)") (class "Default")
      (node (ref "STM32F428Core") (pin "41") (pinfunction "PG13_41") (pintype "passive"))
    )
    (net (code "116") (name "unconnected-(STM32F428Core-PG14-Pad13)") (class "Default")
      (node (ref "STM32F428Core") (pin "13") (pinfunction "PG14_13") (pintype "passive"))
    )
    (net (code "117") (name "unconnected-(STM32F428Core-PH15-Pad73)") (class "Default")
      (node (ref "STM32F428Core") (pin "73") (pinfunction "PH15_73") (pintype "passive"))
    )
    (net (code "118") (name "unconnected-(STM32F428Core-VBAT-Pad60)") (class "Default")
      (node (ref "STM32F428Core") (pin "60") (pinfunction "VBAT_60") (pintype "passive"))
    )
  )
)
